# SMD.net
KiCad netlist of a schematic drawn in EAGLE
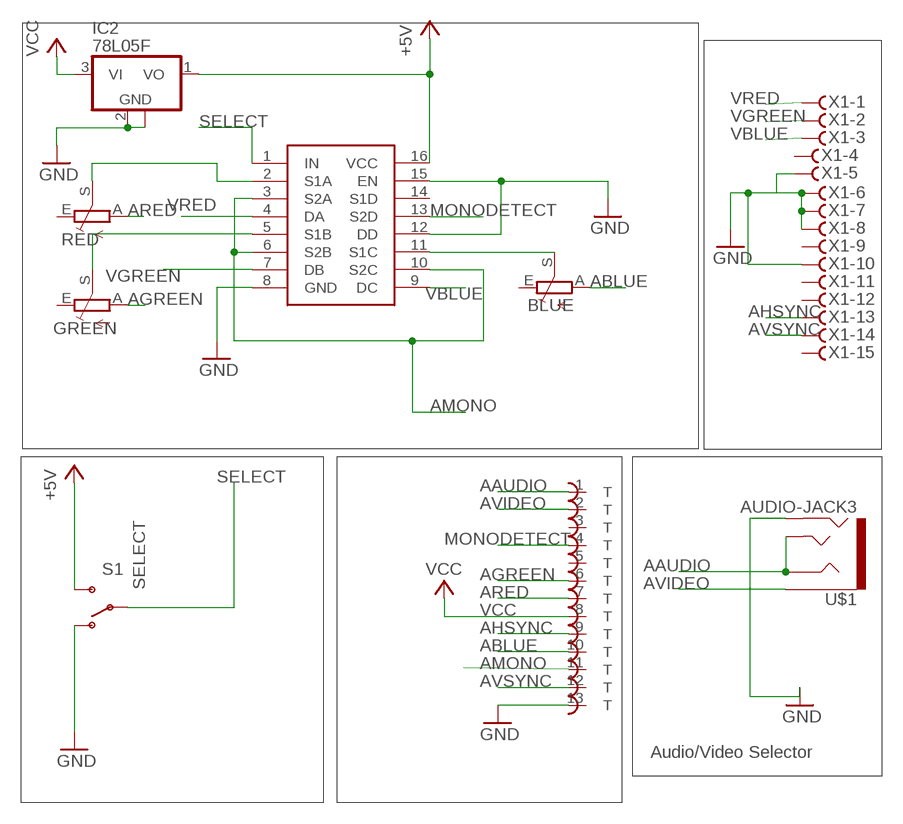
[diagram p0: schematic, sheet 1]

(export (version "E")
  (design (tool "Eeschema 10.0.6"))
  (components
    (comp (ref "ATARIOUT")
      (value "DIN13T")
      (footprint "eagle-import:ADADS")
      (libsource (lib "eagle-import") (part "DIN13T"))
    )
    (comp (ref "BLUE")
      (value "TRIM_EU-CA6H")
      (footprint "eagle-import:CA6H")
      (libsource (lib "eagle-import") (part "TRIM_EU-CA6H"))
    )
    (comp (ref "GREEN")
      (value "TRIM_EU-CA6H")
      (footprint "eagle-import:CA6H")
      (libsource (lib "eagle-import") (part "TRIM_EU-CA6H"))
    )
    (comp (ref "IC2")
      (value "78L05F")
      (footprint "eagle-import:SOT89")
      (libsource (lib "eagle-import") (part "78LF05"))
    )
    (comp (ref "RED")
      (value "TRIM_EU-CA6H")
      (footprint "eagle-import:CA6H")
      (libsource (lib "eagle-import") (part "TRIM_EU-CA6H"))
    )
    (comp (ref "S1")
      (value "SWITCH-SPDT-SMD-A")
      (footprint "eagle-import:SWITCH-SPST-SMD-A")
      (libsource (lib "eagle-import") (part "SWITCH-SPDT-SMD-A"))
    )
    (comp (ref "TS5V330")
      (value "V330")
      (footprint "eagle-import:SOIC16N")
      (libsource (lib "eagle-import") (part "V330"))
    )
    (comp (ref "U$1")
      (value "AUDIO-JACK3")
      (footprint "eagle-import:AUDIO-JACK-TRRS-SMD")
      (libsource (lib "eagle-import") (part "AUDIO-JACK3"))
    )
    (comp (ref "X1")
      (value "F15HDVS")
      (footprint "eagle-import:HDF15V")
      (libsource (lib "eagle-import") (part "F15?SHDV"))
    )
  )
  (nets
    (net (code "1") (name "+5V") (class "Default")
      (node (ref "IC2") (pin "1") (pinfunction "VO_1") (pintype "passive"))
      (node (ref "S1") (pin "3") (pinfunction "S_3") (pintype "passive"))
      (node (ref "TS5V330") (pin "16") (pinfunction "VCC_16") (pintype "bidirectional"))
    )
    (net (code "2") (name "/AAUDIO") (class "Default")
      (node (ref "ATARIOUT") (pin "1") (pinfunction "T_1") (pintype "passive"))
      (node (ref "U$1") (pin "RING1") (pinfunction "RING1_RING1") (pintype "bidirectional"))
      (node (ref "U$1") (pin "TIP") (pinfunction "TIP_TIP") (pintype "bidirectional"))
    )
    (net (code "3") (name "/ABLUE") (class "Default")
      (node (ref "ATARIOUT") (pin "10") (pinfunction "T_10") (pintype "passive"))
      (node (ref "BLUE") (pin "A") (pinfunction "A_A") (pintype "passive"))
    )
    (net (code "4") (name "/AGREEN") (class "Default")
      (node (ref "ATARIOUT") (pin "6") (pinfunction "T_6") (pintype "passive"))
      (node (ref "GREEN") (pin "A") (pinfunction "A_A") (pintype "passive"))
    )
    (net (code "5") (name "/AHSYNC") (class "Default")
      (node (ref "ATARIOUT") (pin "9") (pinfunction "T_9") (pintype "passive"))
      (node (ref "X1") (pin "13") (pinfunction "F_13") (pintype "passive"))
    )
    (net (code "6") (name "/AMONO") (class "Default")
      (node (ref "ATARIOUT") (pin "11") (pinfunction "T_11") (pintype "passive"))
      (node (ref "TS5V330") (pin "10") (pinfunction "S2C_10") (pintype "bidirectional"))
      (node (ref "TS5V330") (pin "3") (pinfunction "S2A_3") (pintype "bidirectional"))
      (node (ref "TS5V330") (pin "6") (pinfunction "S2B_6") (pintype "bidirectional"))
    )
    (net (code "7") (name "/ARED") (class "Default")
      (node (ref "ATARIOUT") (pin "7") (pinfunction "T_7") (pintype "passive"))
      (node (ref "RED") (pin "A") (pinfunction "A_A") (pintype "passive"))
    )
    (net (code "8") (name "/AVIDEO") (class "Default")
      (node (ref "ATARIOUT") (pin "2") (pinfunction "T_2") (pintype "passive"))
      (node (ref "U$1") (pin "EARTH") (pinfunction "EARTH_EARTH") (pintype "bidirectional"))
    )
    (net (code "9") (name "/AVSYNC") (class "Default")
      (node (ref "ATARIOUT") (pin "12") (pinfunction "T_12") (pintype "passive"))
      (node (ref "X1") (pin "14") (pinfunction "F_14") (pintype "passive"))
    )
    (net (code "10") (name "/MONODETECT") (class "Default")
      (node (ref "ATARIOUT") (pin "4") (pinfunction "T_4") (pintype "passive"))
      (node (ref "TS5V330") (pin "13") (pinfunction "S2D_13") (pintype "bidirectional"))
    )
    (net (code "11") (name "/SELECT") (class "Default")
      (node (ref "S1") (pin "2") (pinfunction "P_2") (pintype "passive"))
      (node (ref "TS5V330") (pin "1") (pinfunction "IN_1") (pintype "bidirectional"))
    )
    (net (code "12") (name "/VBLUE") (class "Default")
      (node (ref "TS5V330") (pin "9") (pinfunction "DC_9") (pintype "bidirectional"))
      (node (ref "X1") (pin "3") (pinfunction "F_3") (pintype "passive"))
    )
    (net (code "13") (name "/VGREEN") (class "Default")
      (node (ref "TS5V330") (pin "7") (pinfunction "DB_7") (pintype "bidirectional"))
      (node (ref "X1") (pin "2") (pinfunction "F_2") (pintype "passive"))
    )
    (net (code "14") (name "/VRED") (class "Default")
      (node (ref "TS5V330") (pin "4") (pinfunction "DA_4") (pintype "bidirectional"))
      (node (ref "X1") (pin "1") (pinfunction "F_1") (pintype "passive"))
    )
    (net (code "15") (name "GND") (class "Default")
      (node (ref "ATARIOUT") (pin "13") (pinfunction "T_13") (pintype "passive"))
      (node (ref "IC2") (pin "2") (pinfunction "GND_2") (pintype "passive"))
      (node (ref "IC2") (pin "2@1") (pinfunction "GND_2@1") (pintype "passive"))
      (node (ref "S1") (pin "1") (pinfunction "O_1") (pintype "passive"))
      (node (ref "TS5V330") (pin "12") (pinfunction "DD_12") (pintype "bidirectional"))
      (node (ref "TS5V330") (pin "15") (pinfunction "EN_15") (pintype "bidirectional"))
      (node (ref "TS5V330") (pin "8") (pinfunction "GND_8") (pintype "bidirectional"))
      (node (ref "U$1") (pin "RING2") (pinfunction "RING2_RING2") (pintype "bidirectional"))
      (node (ref "X1") (pin "10") (pinfunction "F_10") (pintype "passive"))
      (node (ref "X1") (pin "5") (pinfunction "F_5") (pintype "passive"))
      (node (ref "X1") (pin "6") (pinfunction "F_6") (pintype "passive"))
      (node (ref "X1") (pin "7") (pinfunction "F_7") (pintype "passive"))
      (node (ref "X1") (pin "8") (pinfunction "F_8") (pintype "passive"))
    )
    (net (code "16") (name "Net-(TS5V330-S1A)") (class "Default")
      (node (ref "RED") (pin "S") (pinfunction "S_S") (pintype "passive"))
      (node (ref "TS5V330") (pin "2") (pinfunction "S1A_2") (pintype "bidirectional"))
    )
    (net (code "17") (name "Net-(TS5V330-S1B)") (class "Default")
      (node (ref "GREEN") (pin "S") (pinfunction "S_S") (pintype "passive"))
      (node (ref "TS5V330") (pin "5") (pinfunction "S1B_5") (pintype "bidirectional"))
    )
    (net (code "18") (name "Net-(TS5V330-S1C)") (class "Default")
      (node (ref "BLUE") (pin "S") (pinfunction "S_S") (pintype "passive"))
      (node (ref "TS5V330") (pin "11") (pinfunction "S1C_11") (pintype "bidirectional"))
    )
    (net (code "19") (name "VCC") (class "Default")
      (node (ref "ATARIOUT") (pin "8") (pinfunction "T_8") (pintype "passive"))
      (node (ref "IC2") (pin "3") (pinfunction "VI_3") (pintype "input"))
    )
    (net (code "20") (name "unconnected-(ATARIOUTG-T-Pad3)") (class "Default")
      (node (ref "ATARIOUT") (pin "3") (pinfunction "T_3") (pintype "passive"))
    )
    (net (code "21") (name "unconnected-(ATARIOUTI-T-Pad5)") (class "Default")
      (node (ref "ATARIOUT") (pin "5") (pinfunction "T_5") (pintype "passive"))
    )
    (net (code "22") (name "unconnected-(BLUE-PadE)") (class "Default")
      (node (ref "BLUE") (pin "E") (pinfunction "E_E") (pintype "passive"))
    )
    (net (code "23") (name "unconnected-(GREEN-PadE)") (class "Default")
      (node (ref "GREEN") (pin "E") (pinfunction "E_E") (pintype "passive"))
    )
    (net (code "24") (name "unconnected-(RED-PadE)") (class "Default")
      (node (ref "RED") (pin "E") (pinfunction "E_E") (pintype "passive"))
    )
    (net (code "25") (name "unconnected-(TS5V330-S1D-Pad14)") (class "Default")
      (node (ref "TS5V330") (pin "14") (pinfunction "S1D_14") (pintype "bidirectional"))
    )
    (net (code "26") (name "unconnected-(X1C-F-Pad11)") (class "Default")
      (node (ref "X1") (pin "11") (pinfunction "F_11") (pintype "passive"))
    )
    (net (code "27") (name "unconnected-(X1D-F-Pad12)") (class "Default")
      (node (ref "X1") (pin "12") (pinfunction "F_12") (pintype "passive"))
    )
    (net (code "28") (name "unconnected-(X1G-F-Pad15)") (class "Default")
      (node (ref "X1") (pin "15") (pinfunction "F_15") (pintype "passive"))
    )
    (net (code "29") (name "unconnected-(X1J-F-Pad4)") (class "Default")
      (node (ref "X1") (pin "4") (pinfunction "F_4") (pintype "passive"))
    )
    (net (code "30") (name "unconnected-(X1O-F-Pad9)") (class "Default")
      (node (ref "X1") (pin "9") (pinfunction "F_9") (pintype "passive"))
    )
  )
)
